# Buzz_AND_PINS.net
KiCad netlist of a schematic drawn in Altium Designer
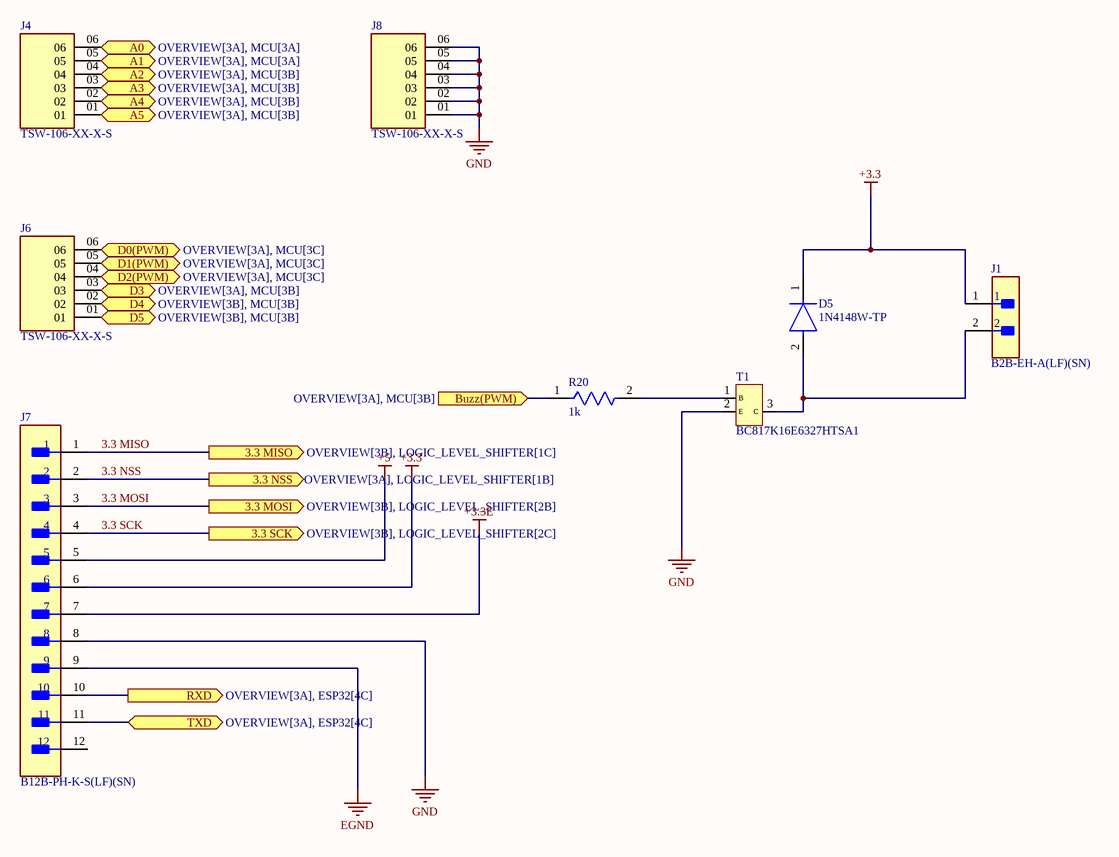
[diagram p0: Buzz_AND_PINS.SchDoc]

(export (version "E")
  (design (tool "Eeschema 10.0.6"))
  (components
    (comp (ref "D5")
      (value "1N4148W-TP")
      (footprint "FP-SOD-123-IPC_A")
      (description "DIODE GEN PURP 100V 150MA SOD123")
      (libsource (lib "Altium Content Vault") (part "d7152d700b627762746794eb795d46e"))
    )
    (comp (ref "J1")
      (value "B2B-EH-A(LF)(SN)")
      (footprint "FP-B2B-EH-A_LF_SN-MFG")
      (description "CONN HEADER VERT 2POS 2.5MM")
      (libsource (lib "Altium Content Vault") (part "3bc925449376181038e59eaffc5286c"))
    )
    (comp (ref "J4")
      (value "TSW-106-XX-X-S")
      (footprint "SAMTEC_TSW-106-XX-X-S")
      (description "Connector Header Through Hole 6 position 0.100 (2.54mm)")
      (fields (field (name "MF") "Samtec") (field (name "MP") "TSW-106-26-T-S"))
      (libsource (lib "RFID") (part "TSW-106-XX-X-S"))
    )
    (comp (ref "J6")
      (value "TSW-106-XX-X-S")
      (footprint "SAMTEC_TSW-106-XX-X-S")
      (description "Connector Header Through Hole 6 position 0.100 (2.54mm)")
      (fields (field (name "MF") "Samtec") (field (name "MP") "TSW-106-26-T-S"))
      (libsource (lib "RFID") (part "TSW-106-XX-X-S"))
    )
    (comp (ref "J7")
      (value "B12B-PH-K-S(LF)(SN)")
      (footprint "FP-B12B-PH-K-S_LF_SN-MFG")
      (description "CONN HEADER VERT 12POS 2MM")
      (libsource (lib "Altium Content Vault") (part "d87d8706af15dcceb0cd5655c97e2e6"))
    )
    (comp (ref "J8")
      (value "TSW-106-XX-X-S")
      (footprint "SAMTEC_TSW-106-XX-X-S")
      (description "Connector Header Through Hole 6 position 0.100 (2.54mm)")
      (fields (field (name "MF") "Samtec") (field (name "MP") "TSW-106-26-T-S"))
      (libsource (lib "RFID") (part "TSW-106-XX-X-S"))
    )
    (comp (ref "R20")
      (value "1k")
      (footprint "FP-MCA1206-IPC_C")
      (description "Res MC Professional Thin Film 1206 1kΩ 1% 0.4W ±50ppm/°C Molded Paper T/R")
      (fields (field (name "TOLERANCE") "1%"))
      (libsource (lib "Altium Content Vault") (part "1029c3af85768c4190bb7ad29bc67b5"))
    )
    (comp (ref "T1")
      (value "BC817K16E6327HTSA1")
      (footprint "SOT95P245X110-3N")
      (description "Small Signal Bipolar Transistor, 0.5A I(C), 45V V(BR)CEO, 1-Element, NPN, Silicon")
      (fields (field (name "MANUFACTURER") "Infineon"))
      (libsource (lib "RFID") (part "BC817K16E6327HTSA1"))
    )
  )
  (nets
    (net (code "1") (name "+3.3") (class "Default")
      (node (ref "D5") (pin "1") (pinfunction "C_1") (pintype "passive"))
      (node (ref "J1") (pin "1") (pinfunction "1_1") (pintype "passive"))
      (node (ref "J7") (pin "6") (pinfunction "6_6") (pintype "passive"))
    )
    (net (code "2") (name "+3.3E") (class "Default")
      (node (ref "J7") (pin "7") (pinfunction "7_7") (pintype "passive"))
    )
    (net (code "3") (name "+5") (class "Default")
      (node (ref "J7") (pin "5") (pinfunction "5_5") (pintype "passive"))
    )
    (net (code "4") (name "/3.3 MISO") (class "Default")
      (node (ref "J7") (pin "1") (pinfunction "1_1") (pintype "passive"))
    )
    (net (code "5") (name "/3.3 MOSI") (class "Default")
      (node (ref "J7") (pin "3") (pinfunction "3_3") (pintype "passive"))
    )
    (net (code "6") (name "/3.3 NSS") (class "Default")
      (node (ref "J7") (pin "2") (pinfunction "2_2") (pintype "passive"))
    )
    (net (code "7") (name "/3.3 SCK") (class "Default")
      (node (ref "J7") (pin "4") (pinfunction "4_4") (pintype "passive"))
    )
    (net (code "8") (name "/A0") (class "Default")
      (node (ref "J4") (pin "06") (pinfunction "06_06") (pintype "passive"))
    )
    (net (code "9") (name "/A1") (class "Default")
      (node (ref "J4") (pin "05") (pinfunction "05_05") (pintype "passive"))
    )
    (net (code "10") (name "/A2") (class "Default")
      (node (ref "J4") (pin "04") (pinfunction "04_04") (pintype "passive"))
    )
    (net (code "11") (name "/A3") (class "Default")
      (node (ref "J4") (pin "03") (pinfunction "03_03") (pintype "passive"))
    )
    (net (code "12") (name "/A4") (class "Default")
      (node (ref "J4") (pin "02") (pinfunction "02_02") (pintype "passive"))
    )
    (net (code "13") (name "/A5") (class "Default")
      (node (ref "J4") (pin "01") (pinfunction "01_01") (pintype "passive"))
    )
    (net (code "14") (name "/Buzz(PWM)") (class "Default")
      (node (ref "R20") (pin "1") (pinfunction "1_1") (pintype "passive"))
    )
    (net (code "15") (name "/D0(PWM)") (class "Default")
      (node (ref "J6") (pin "06") (pinfunction "06_06") (pintype "passive"))
    )
    (net (code "16") (name "/D1(PWM)") (class "Default")
      (node (ref "J6") (pin "05") (pinfunction "05_05") (pintype "passive"))
    )
    (net (code "17") (name "/D2(PWM)") (class "Default")
      (node (ref "J6") (pin "04") (pinfunction "04_04") (pintype "passive"))
    )
    (net (code "18") (name "/D3") (class "Default")
      (node (ref "J6") (pin "03") (pinfunction "03_03") (pintype "passive"))
    )
    (net (code "19") (name "/D4") (class "Default")
      (node (ref "J6") (pin "02") (pinfunction "02_02") (pintype "passive"))
    )
    (net (code "20") (name "/D5") (class "Default")
      (node (ref "J6") (pin "01") (pinfunction "01_01") (pintype "passive"))
    )
    (net (code "21") (name "/RXD") (class "Default")
      (node (ref "J7") (pin "10") (pinfunction "10_10") (pintype "passive"))
    )
    (net (code "22") (name "/TXD") (class "Default")
      (node (ref "J7") (pin "11") (pinfunction "11_11") (pintype "passive"))
    )
    (net (code "23") (name "EGND") (class "Default")
      (node (ref "J7") (pin "9") (pinfunction "9_9") (pintype "passive"))
    )
    (net (code "24") (name "GND") (class "Default")
      (node (ref "J7") (pin "8") (pinfunction "8_8") (pintype "passive"))
      (node (ref "J8") (pin "01") (pinfunction "01_01") (pintype "passive"))
      (node (ref "J8") (pin "02") (pinfunction "02_02") (pintype "passive"))
      (node (ref "J8") (pin "03") (pinfunction "03_03") (pintype "passive"))
      (node (ref "J8") (pin "04") (pinfunction "04_04") (pintype "passive"))
      (node (ref "J8") (pin "05") (pinfunction "05_05") (pintype "passive"))
      (node (ref "J8") (pin "06") (pinfunction "06_06") (pintype "passive"))
      (node (ref "T1") (pin "2") (pinfunction "E_2") (pintype "passive"))
    )
    (net (code "25") (name "Net-(D5-A)") (class "Default")
      (node (ref "D5") (pin "2") (pinfunction "A_2") (pintype "passive"))
      (node (ref "J1") (pin "2") (pinfunction "2_2") (pintype "passive"))
      (node (ref "T1") (pin "3") (pinfunction "C_3") (pintype "bidirectional"))
    )
    (net (code "26") (name "Net-(T1-B)") (class "Default")
      (node (ref "R20") (pin "2") (pinfunction "2_2") (pintype "passive"))
      (node (ref "T1") (pin "1") (pinfunction "B_1") (pintype "bidirectional"))
    )
    (net (code "27") (name "unconnected-(J7-Pad12)") (class "Default")
      (node (ref "J7") (pin "12") (pinfunction "12_12") (pintype "passive"))
    )
  )
)
